# RemoteLora.net
KiCad netlist of a schematic drawn in Altium Designer
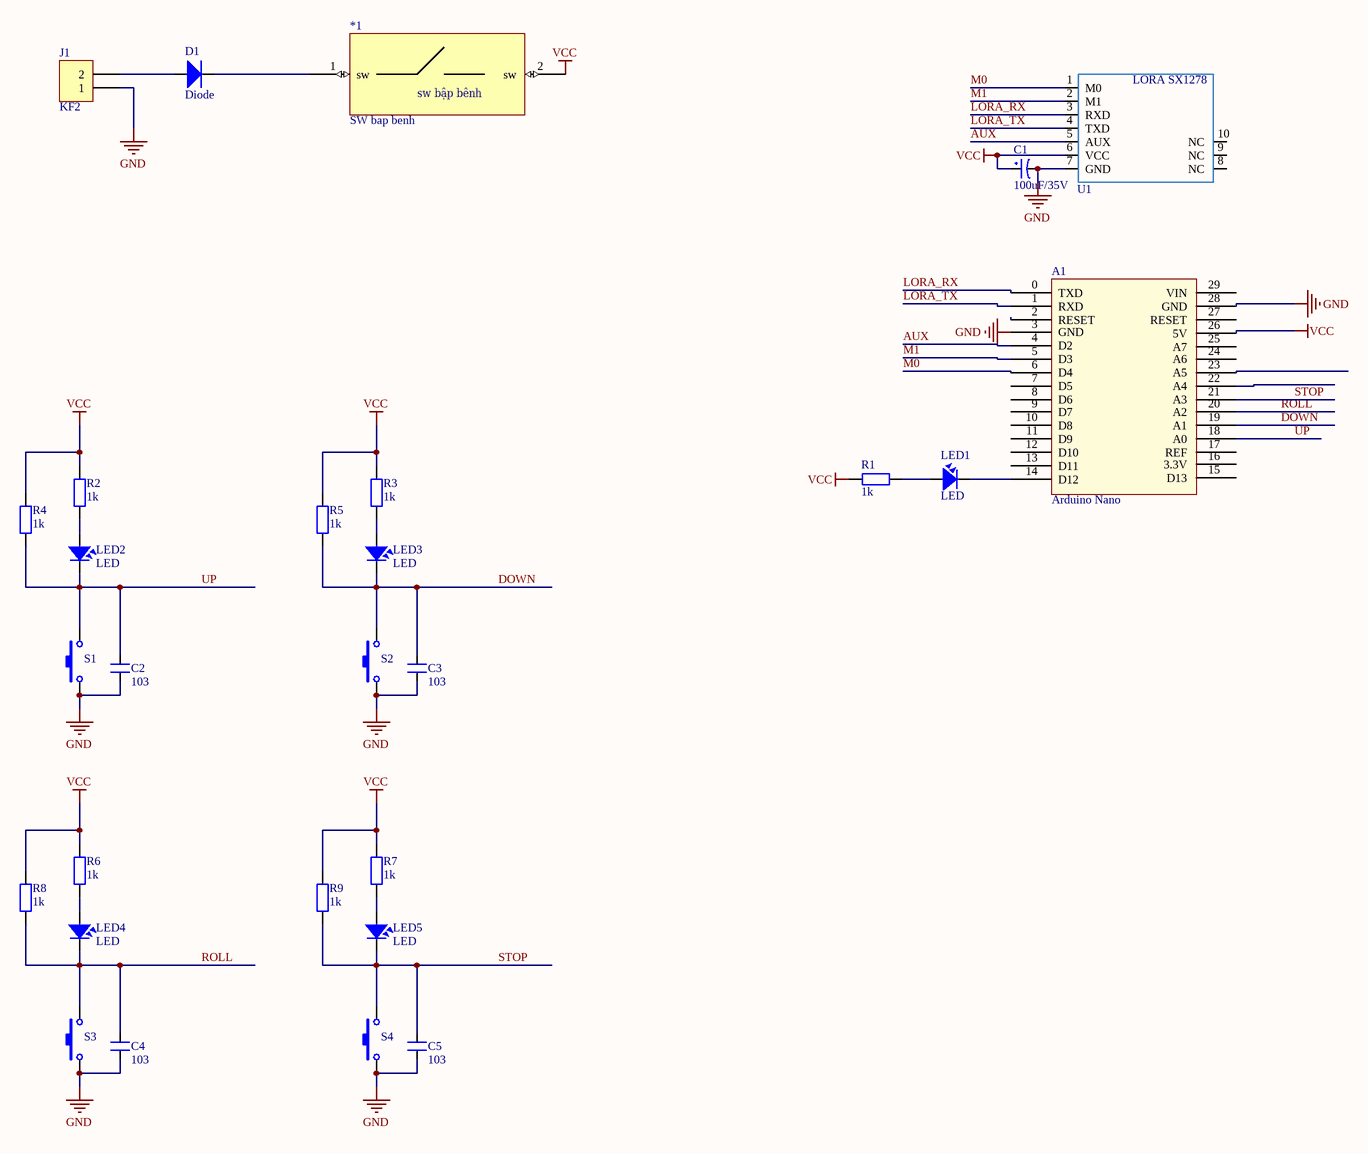
[diagram p0: RemoteLora.SchDoc]

(export (version "E")
  (design (tool "Eeschema 10.0.6"))
  (components
    (comp (ref "*1")
      (value "SW bap benh")
      (footprint "SW bapbenh")
      (libsource (lib "Tesla_Thinh") (part "SW bap benh"))
    )
    (comp (ref "A1")
      (value "Arduino Nano")
      (footprint "Arduino Nano")
      (libsource (lib "OBIT_TESLA") (part "Arduino Nano"))
    )
    (comp (ref "C1")
      (value "100uF/35V")
      (footprint "CP1.5/3.4")
      (description "Cap 100uF/35V - 470uF/16V")
      (libsource (lib "OBIT_TESLA") (part "CP3"))
    )
    (comp (ref "C2")
      (value "103")
      (footprint "SM-0805")
      (description "Cap SMD")
      (libsource (lib "OBIT_TESLA") (part "CM"))
    )
    (comp (ref "C3")
      (value "103")
      (footprint "SM-0805")
      (description "Cap SMD")
      (libsource (lib "OBIT_TESLA") (part "CM"))
    )
    (comp (ref "C4")
      (value "103")
      (footprint "SM-0805")
      (description "Cap SMD")
      (libsource (lib "OBIT_TESLA") (part "CM"))
    )
    (comp (ref "C5")
      (value "103")
      (footprint "SM-0805")
      (description "Cap SMD")
      (libsource (lib "OBIT_TESLA") (part "CM"))
    )
    (comp (ref "D1") (value "Diode") (footprint "D0.5A") (libsource (lib "OBIT_TESLA") (part "Diode")))
    (comp (ref "J1")
      (value "KF2")
      (footprint "KF2-3.5")
      (fields
        (field (name "MANUFACTURER") "Würth Elektronik eiSos GmbH")
        (field (name "PARTNO") "691103110002")
        (field (name "CREATED BY") "Karrer Zheng")
      )
      (libsource (lib "OBIT_TESLA") (part "KF2"))
    )
    (comp (ref "LED1") (value "LED") (footprint "LED-5-BLUE") (libsource (lib "OBIT_TESLA") (part "LED")))
    (comp (ref "LED2") (value "LED") (footprint "LED-5-BLUE") (libsource (lib "OBIT_TESLA") (part "LED")))
    (comp (ref "LED3") (value "LED") (footprint "LED-5-BLUE") (libsource (lib "OBIT_TESLA") (part "LED")))
    (comp (ref "LED4") (value "LED") (footprint "LED-5-BLUE") (libsource (lib "OBIT_TESLA") (part "LED")))
    (comp (ref "LED5") (value "LED") (footprint "LED-5-BLUE") (libsource (lib "OBIT_TESLA") (part "LED")))
    (comp (ref "R1")
      (value "1k")
      (footprint "RES-1/4W")
      (description "Resistor R1/4W")
      (libsource (lib "OBIT_TESLA") (part "R"))
    )
    (comp (ref "R2")
      (value "1k")
      (footprint "RES-1/4W")
      (description "Resistor R1/4W")
      (libsource (lib "OBIT_TESLA") (part "R"))
    )
    (comp (ref "R3")
      (value "1k")
      (footprint "RES-1/4W")
      (description "Resistor R1/4W")
      (libsource (lib "OBIT_TESLA") (part "R"))
    )
    (comp (ref "R4")
      (value "1k")
      (footprint "RES-1/4W")
      (description "Resistor R1/4W")
      (libsource (lib "OBIT_TESLA") (part "R"))
    )
    (comp (ref "R5")
      (value "1k")
      (footprint "RES-1/4W")
      (description "Resistor R1/4W")
      (libsource (lib "OBIT_TESLA") (part "R"))
    )
    (comp (ref "R6")
      (value "1k")
      (footprint "RES-1/4W")
      (description "Resistor R1/4W")
      (libsource (lib "OBIT_TESLA") (part "R"))
    )
    (comp (ref "R7")
      (value "1k")
      (footprint "RES-1/4W")
      (description "Resistor R1/4W")
      (libsource (lib "OBIT_TESLA") (part "R"))
    )
    (comp (ref "R8")
      (value "1k")
      (footprint "RES-1/4W")
      (description "Resistor R1/4W")
      (libsource (lib "OBIT_TESLA") (part "R"))
    )
    (comp (ref "R9")
      (value "1k")
      (footprint "RES-1/4W")
      (description "Resistor R1/4W")
      (libsource (lib "OBIT_TESLA") (part "R"))
    )
    (comp (ref "S1")
      (value "SW")
      (footprint "BUTTON  ROUND")
      (description "Switch-Button")
      (fields (field (name "PUBLISHER") "Altium Limited"))
      (libsource (lib "OBIT_TESLA") (part "SW-Button"))
    )
    (comp (ref "S2")
      (value "SW")
      (footprint "BUTTON  ROUND")
      (description "Switch-Button")
      (fields (field (name "PUBLISHER") "Altium Limited"))
      (libsource (lib "OBIT_TESLA") (part "SW-Button"))
    )
    (comp (ref "S3")
      (value "SW")
      (footprint "BUTTON  ROUND")
      (description "Switch-Button")
      (fields (field (name "PUBLISHER") "Altium Limited"))
      (libsource (lib "OBIT_TESLA") (part "SW-Button"))
    )
    (comp (ref "S4")
      (value "SW")
      (footprint "BUTTON  ROUND")
      (description "Switch-Button")
      (fields (field (name "PUBLISHER") "Altium Limited"))
      (libsource (lib "OBIT_TESLA") (part "SW-Button"))
    )
    (comp (ref "U1")
      (value "Lora SX1278 UART")
      (footprint "Lora_uart_sx1278")
      (libsource (lib "OBIT_TESLA") (part "Lora SX1278 UART"))
    )
  )
  (nets
    (net (code "1") (name "/AUX") (class "Default")
      (node (ref "A1") (pin "4") (pinfunction "D2_4") (pintype "passive"))
      (node (ref "U1") (pin "5") (pinfunction "AUX_5") (pintype "passive"))
    )
    (net (code "2") (name "/DOWN") (class "Default")
      (node (ref "A1") (pin "19") (pinfunction "A1_19") (pintype "passive"))
      (node (ref "C3") (pin "2") (pinfunction "2_2") (pintype "passive"))
      (node (ref "LED3") (pin "2") (pinfunction "2_2") (pintype "passive"))
      (node (ref "R5") (pin "1") (pinfunction "1_1") (pintype "passive"))
      (node (ref "S2") (pin "2") (pinfunction "2_2") (pintype "passive"))
    )
    (net (code "3") (name "/LORA_RX") (class "Default")
      (node (ref "A1") (pin "0") (pinfunction "TXD_0") (pintype "passive"))
      (node (ref "U1") (pin "3") (pinfunction "RXD_3") (pintype "passive"))
    )
    (net (code "4") (name "/LORA_TX") (class "Default")
      (node (ref "A1") (pin "1") (pinfunction "RXD_1") (pintype "passive"))
      (node (ref "U1") (pin "4") (pinfunction "TXD_4") (pintype "passive"))
    )
    (net (code "5") (name "/M0") (class "Default")
      (node (ref "A1") (pin "6") (pinfunction "D4_6") (pintype "passive"))
      (node (ref "U1") (pin "1") (pinfunction "M0_1") (pintype "passive"))
    )
    (net (code "6") (name "/M1") (class "Default")
      (node (ref "A1") (pin "5") (pinfunction "D3_5") (pintype "passive"))
      (node (ref "U1") (pin "2") (pinfunction "M1_2") (pintype "passive"))
    )
    (net (code "7") (name "/ROLL") (class "Default")
      (node (ref "A1") (pin "20") (pinfunction "A2_20") (pintype "passive"))
      (node (ref "C4") (pin "2") (pinfunction "2_2") (pintype "passive"))
      (node (ref "LED4") (pin "2") (pinfunction "2_2") (pintype "passive"))
      (node (ref "R8") (pin "1") (pinfunction "1_1") (pintype "passive"))
      (node (ref "S3") (pin "2") (pinfunction "2_2") (pintype "passive"))
    )
    (net (code "8") (name "/STOP") (class "Default")
      (node (ref "A1") (pin "21") (pinfunction "A3_21") (pintype "passive"))
      (node (ref "C5") (pin "2") (pinfunction "2_2") (pintype "passive"))
      (node (ref "LED5") (pin "2") (pinfunction "2_2") (pintype "passive"))
      (node (ref "R9") (pin "1") (pinfunction "1_1") (pintype "passive"))
      (node (ref "S4") (pin "2") (pinfunction "2_2") (pintype "passive"))
    )
    (net (code "9") (name "/UP") (class "Default")
      (node (ref "A1") (pin "18") (pinfunction "A0_18") (pintype "passive"))
      (node (ref "C2") (pin "2") (pinfunction "2_2") (pintype "passive"))
      (node (ref "LED2") (pin "2") (pinfunction "2_2") (pintype "passive"))
      (node (ref "R4") (pin "1") (pinfunction "1_1") (pintype "passive"))
      (node (ref "S1") (pin "2") (pinfunction "2_2") (pintype "passive"))
    )
    (net (code "10") (name "GND") (class "Default")
      (node (ref "A1") (pin "28") (pinfunction "GND_28") (pintype "passive"))
      (node (ref "A1") (pin "3") (pinfunction "GND_3") (pintype "passive"))
      (node (ref "C1") (pin "2") (pinfunction "2_2") (pintype "passive"))
      (node (ref "C2") (pin "1") (pinfunction "1_1") (pintype "passive"))
      (node (ref "C3") (pin "1") (pinfunction "1_1") (pintype "passive"))
      (node (ref "C4") (pin "1") (pinfunction "1_1") (pintype "passive"))
      (node (ref "C5") (pin "1") (pinfunction "1_1") (pintype "passive"))
      (node (ref "J1") (pin "1") (pinfunction "1_1") (pintype "passive"))
      (node (ref "S1") (pin "1") (pinfunction "1_1") (pintype "passive"))
      (node (ref "S2") (pin "1") (pinfunction "1_1") (pintype "passive"))
      (node (ref "S3") (pin "1") (pinfunction "1_1") (pintype "passive"))
      (node (ref "S4") (pin "1") (pinfunction "1_1") (pintype "passive"))
      (node (ref "U1") (pin "7") (pinfunction "GND_7") (pintype "passive"))
    )
    (net (code "11") (name "Net-(*1-sw-Pad1)") (class "Default")
      (node (ref "*1") (pin "1") (pinfunction "sw_1") (pintype "bidirectional"))
      (node (ref "D1") (pin "2") (pinfunction "2_2") (pintype "passive"))
    )
    (net (code "12") (name "Net-(A1-D12)") (class "Default")
      (node (ref "A1") (pin "14") (pinfunction "D12_14") (pintype "passive"))
      (node (ref "LED1") (pin "2") (pinfunction "2_2") (pintype "passive"))
    )
    (net (code "13") (name "Net-(D1-Pad1)") (class "Default")
      (node (ref "D1") (pin "1") (pinfunction "1_1") (pintype "passive"))
      (node (ref "J1") (pin "2") (pinfunction "2_2") (pintype "passive"))
    )
    (net (code "14") (name "Net-(LED1-Pad1)") (class "Default")
      (node (ref "LED1") (pin "1") (pinfunction "1_1") (pintype "passive"))
      (node (ref "R1") (pin "2") (pinfunction "2_2") (pintype "passive"))
    )
    (net (code "15") (name "Net-(LED2-Pad1)") (class "Default")
      (node (ref "LED2") (pin "1") (pinfunction "1_1") (pintype "passive"))
      (node (ref "R2") (pin "1") (pinfunction "1_1") (pintype "passive"))
    )
    (net (code "16") (name "Net-(LED3-Pad1)") (class "Default")
      (node (ref "LED3") (pin "1") (pinfunction "1_1") (pintype "passive"))
      (node (ref "R3") (pin "1") (pinfunction "1_1") (pintype "passive"))
    )
    (net (code "17") (name "Net-(LED4-Pad1)") (class "Default")
      (node (ref "LED4") (pin "1") (pinfunction "1_1") (pintype "passive"))
      (node (ref "R6") (pin "1") (pinfunction "1_1") (pintype "passive"))
    )
    (net (code "18") (name "Net-(LED5-Pad1)") (class "Default")
      (node (ref "LED5") (pin "1") (pinfunction "1_1") (pintype "passive"))
      (node (ref "R7") (pin "1") (pinfunction "1_1") (pintype "passive"))
    )
    (net (code "19") (name "VCC") (class "Default")
      (node (ref "*1") (pin "2") (pinfunction "sw_2") (pintype "bidirectional"))
      (node (ref "A1") (pin "26") (pinfunction "5V_26") (pintype "passive"))
      (node (ref "C1") (pin "1") (pinfunction "1_1") (pintype "passive"))
      (node (ref "R1") (pin "1") (pinfunction "1_1") (pintype "passive"))
      (node (ref "R2") (pin "2") (pinfunction "2_2") (pintype "passive"))
      (node (ref "R3") (pin "2") (pinfunction "2_2") (pintype "passive"))
      (node (ref "R4") (pin "2") (pinfunction "2_2") (pintype "passive"))
      (node (ref "R5") (pin "2") (pinfunction "2_2") (pintype "passive"))
      (node (ref "R6") (pin "2") (pinfunction "2_2") (pintype "passive"))
      (node (ref "R7") (pin "2") (pinfunction "2_2") (pintype "passive"))
      (node (ref "R8") (pin "2") (pinfunction "2_2") (pintype "passive"))
      (node (ref "R9") (pin "2") (pinfunction "2_2") (pintype "passive"))
      (node (ref "U1") (pin "6") (pinfunction "VCC_6") (pintype "passive"))
    )
    (net (code "20") (name "unconnected-(A1-3.3V-Pad16)") (class "Default")
      (node (ref "A1") (pin "16") (pinfunction "3.3V_16") (pintype "passive"))
    )
    (net (code "21") (name "unconnected-(A1-A4-Pad22)") (class "Default")
      (node (ref "A1") (pin "22") (pinfunction "A4_22") (pintype "passive"))
    )
    (net (code "22") (name "unconnected-(A1-A5-Pad23)") (class "Default")
      (node (ref "A1") (pin "23") (pinfunction "A5_23") (pintype "passive"))
    )
    (net (code "23") (name "unconnected-(A1-A6-Pad24)") (class "Default")
      (node (ref "A1") (pin "24") (pinfunction "A6_24") (pintype "passive"))
    )
    (net (code "24") (name "unconnected-(A1-A7-Pad25)") (class "Default")
      (node (ref "A1") (pin "25") (pinfunction "A7_25") (pintype "passive"))
    )
    (net (code "25") (name "unconnected-(A1-D5-Pad7)") (class "Default")
      (node (ref "A1") (pin "7") (pinfunction "D5_7") (pintype "passive"))
    )
    (net (code "26") (name "unconnected-(A1-D6-Pad8)") (class "Default")
      (node (ref "A1") (pin "8") (pinfunction "D6_8") (pintype "passive"))
    )
    (net (code "27") (name "unconnected-(A1-D7-Pad9)") (class "Default")
      (node (ref "A1") (pin "9") (pinfunction "D7_9") (pintype "passive"))
    )
    (net (code "28") (name "unconnected-(A1-D8-Pad10)") (class "Default")
      (node (ref "A1") (pin "10") (pinfunction "D8_10") (pintype "passive"))
    )
    (net (code "29") (name "unconnected-(A1-D9-Pad11)") (class "Default")
      (node (ref "A1") (pin "11") (pinfunction "D9_11") (pintype "passive"))
    )
    (net (code "30") (name "unconnected-(A1-D10-Pad12)") (class "Default")
      (node (ref "A1") (pin "12") (pinfunction "D10_12") (pintype "passive"))
    )
    (net (code "31") (name "unconnected-(A1-D11-Pad13)") (class "Default")
      (node (ref "A1") (pin "13") (pinfunction "D11_13") (pintype "passive"))
    )
    (net (code "32") (name "unconnected-(A1-D13-Pad15)") (class "Default")
      (node (ref "A1") (pin "15") (pinfunction "D13_15") (pintype "passive"))
    )
    (net (code "33") (name "unconnected-(A1-REF-Pad17)") (class "Default")
      (node (ref "A1") (pin "17") (pinfunction "REF_17") (pintype "passive"))
    )
    (net (code "34") (name "unconnected-(A1-RESET-Pad2)") (class "Default")
      (node (ref "A1") (pin "2") (pinfunction "RESET_2") (pintype "passive"))
    )
    (net (code "35") (name "unconnected-(A1-RESET-Pad27)") (class "Default")
      (node (ref "A1") (pin "27") (pinfunction "RESET_27") (pintype "passive"))
    )
    (net (code "36") (name "unconnected-(A1-VIN-Pad29)") (class "Default")
      (node (ref "A1") (pin "29") (pinfunction "VIN_29") (pintype "passive"))
    )
    (net (code "37") (name "unconnected-(U1-NC-Pad8)") (class "Default")
      (node (ref "U1") (pin "8") (pinfunction "NC_8") (pintype "passive"))
    )
    (net (code "38") (name "unconnected-(U1-NC-Pad9)") (class "Default")
      (node (ref "U1") (pin "9") (pinfunction "NC_9") (pintype "passive"))
    )
    (net (code "39") (name "unconnected-(U1-NC-Pad10)") (class "Default")
      (node (ref "U1") (pin "10") (pinfunction "NC_10") (pintype "passive"))
    )
  )
)
